# MacSet-L-V2_0_0_2.net
KiCad netlist of a schematic drawn in Altium Designer
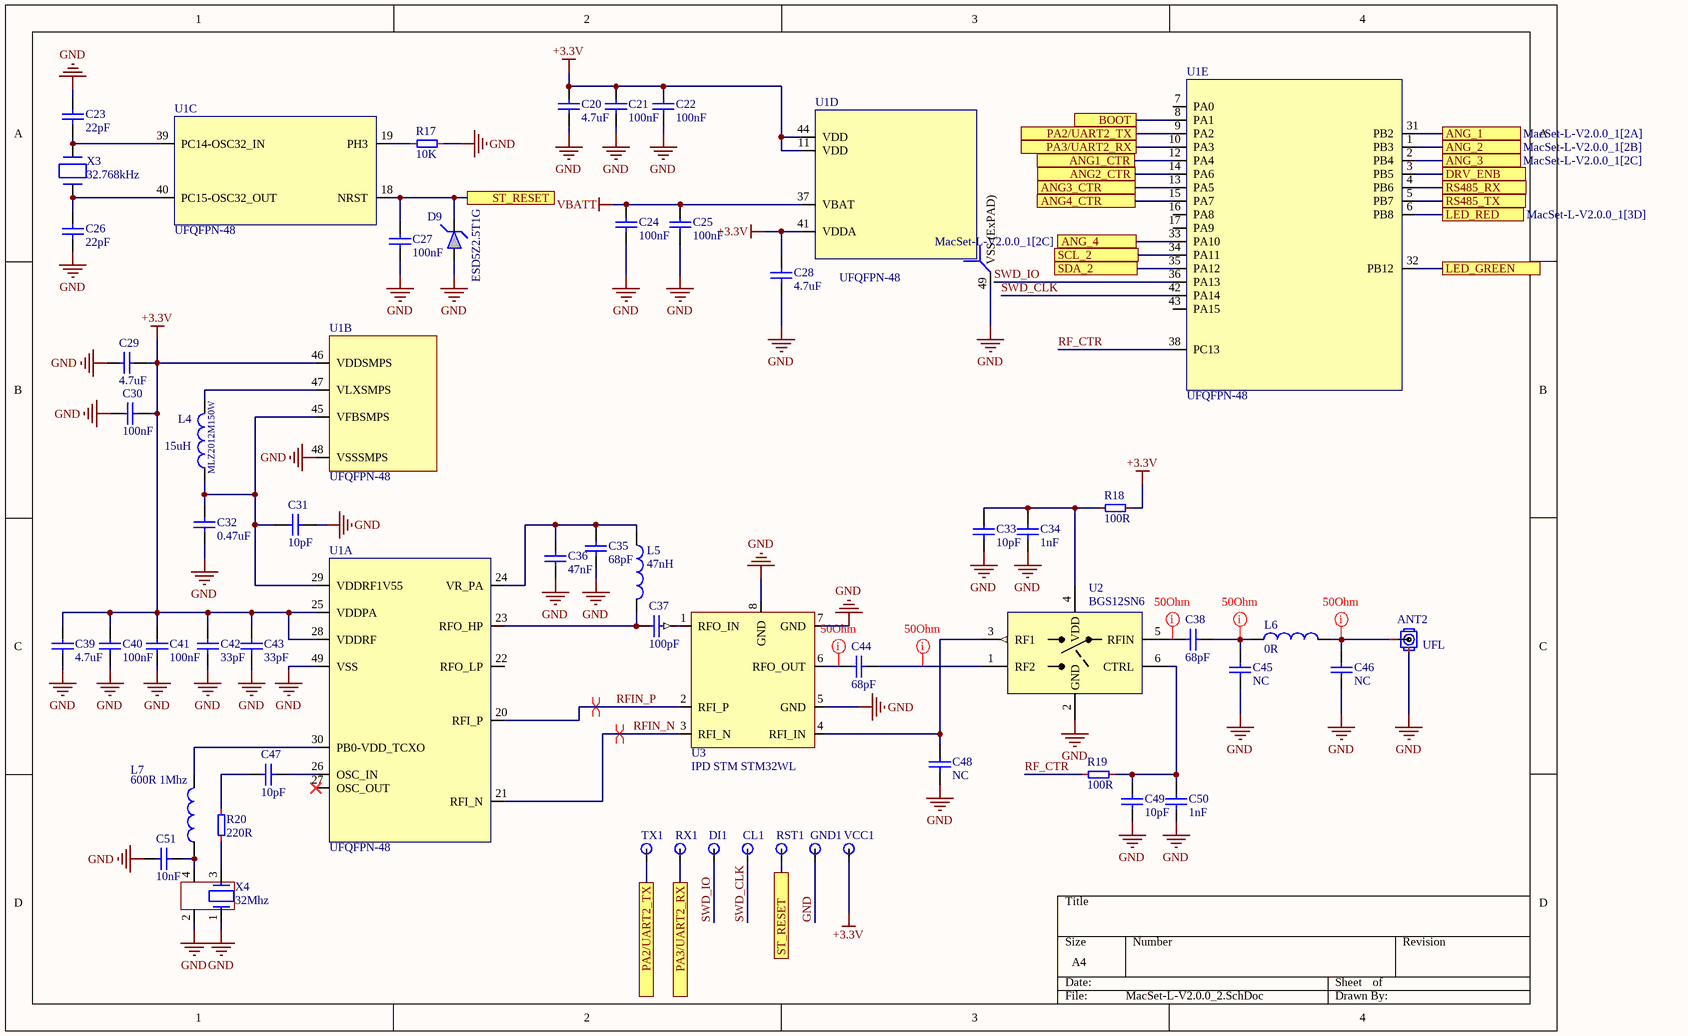
[diagram p0: MacSet-L-V2.0.0_2.SchDoc]

(export (version "E")
  (design (tool "Eeschema 10.0.6"))
  (components
    (comp (ref "ANT2")
      (value "UFL")
      (footprint "UFL")
      (description "SMA Connector")
      (libsource (lib "macnman_3.0") (part "SMA Antenna"))
    )
    (comp (ref "C20")
      (value "4.7uF")
      (footprint "CAP0603")
      (description "MLCC - SMD/SMT 4.7 uF 16 VDC 10% 0603 X5R")
      (fields
        (field (name "MANUFACTURER_PART_NUMBER") "CL10A475KQ8NNNC")
        (field (name "MANUFACTURER") "Samsung Electro-Mechanics")
      )
      (libsource (lib "macnman_2.0") (part "Capa_0603"))
    )
    (comp (ref "C21")
      (value "100nF")
      (footprint "CAP0402")
      (description "Ceramic Capacitor X7R 0402 100nF 16V")
      (fields
        (field (name "MANUFACTURER_PART_NUMBER") "GRM155R71C104JA88D")
        (field (name "MANUFACTURER") "MURATA")
      )
      (libsource (lib "macnman_2.0") (part "Capa_0402"))
    )
    (comp (ref "C22")
      (value "100nF")
      (footprint "CAP0402")
      (description "Ceramic Capacitor X7R 0402 100nF 16V")
      (fields
        (field (name "MANUFACTURER_PART_NUMBER") "GRM155R71C104JA88D")
        (field (name "MANUFACTURER") "MURATA")
      )
      (libsource (lib "macnman_2.0") (part "Capa_0402"))
    )
    (comp (ref "C23")
      (value "22pF")
      (footprint "CAP0402")
      (description "Multilayer Ceramic Capacitors MLCC - SMD/SMT 50 V 22pF C0G 0402 5%")
      (fields
        (field (name "MANUFACTURER_PART_NUMBER") "GCM1555C1H220JA16D")
        (field (name "MANUFACTURER") "Murata")
      )
      (libsource (lib "macnman_2.0") (part "Capa_0402"))
    )
    (comp (ref "C24")
      (value "100nF")
      (footprint "CAP0402")
      (description "Ceramic Capacitor X7R 0402 100nF 16V")
      (fields
        (field (name "MANUFACTURER_PART_NUMBER") "GRM155R71C104JA88D")
        (field (name "MANUFACTURER") "MURATA")
      )
      (libsource (lib "macnman_2.0") (part "Capa_0402"))
    )
    (comp (ref "C25")
      (value "100nF")
      (footprint "CAP0402")
      (description "Ceramic Capacitor X7R 0402 100nF 16V")
      (fields
        (field (name "MANUFACTURER_PART_NUMBER") "GRM155R71C104JA88D")
        (field (name "MANUFACTURER") "MURATA")
      )
      (libsource (lib "macnman_2.0") (part "Capa_0402"))
    )
    (comp (ref "C26")
      (value "22pF")
      (footprint "CAP0402")
      (description "Multilayer Ceramic Capacitors MLCC - SMD/SMT 50 V 22pF C0G 0402 5%")
      (fields
        (field (name "MANUFACTURER_PART_NUMBER") "GCM1555C1H220JA16D")
        (field (name "MANUFACTURER") "Murata")
      )
      (libsource (lib "macnman_2.0") (part "Capa_0402"))
    )
    (comp (ref "C27")
      (value "100nF")
      (footprint "CAP0402")
      (description "Ceramic Capacitor X7R 0402 100nF 16V")
      (fields
        (field (name "MANUFACTURER_PART_NUMBER") "GRM155R71C104JA88D")
        (field (name "MANUFACTURER") "MURATA")
      )
      (libsource (lib "macnman_2.0") (part "Capa_0402"))
    )
    (comp (ref "C28")
      (value "4.7uF")
      (footprint "CAP0603")
      (description "MLCC - SMD/SMT 4.7 uF 16 VDC 10% 0603 X5R")
      (fields
        (field (name "MANUFACTURER_PART_NUMBER") "CL10A475KQ8NNNC")
        (field (name "MANUFACTURER") "Samsung Electro-Mechanics")
      )
      (libsource (lib "macnman_2.0") (part "Capa_0603"))
    )
    (comp (ref "C29")
      (value "4.7uF")
      (footprint "CAP0603")
      (description "MLCC - SMD/SMT 4.7 uF 16 VDC 10% 0603 X5R")
      (fields
        (field (name "MANUFACTURER_PART_NUMBER") "CL10A475KQ8NNNC")
        (field (name "MANUFACTURER") "Samsung Electro-Mechanics")
      )
      (libsource (lib "macnman_2.0") (part "Capa_0603"))
    )
    (comp (ref "C30")
      (value "100nF")
      (footprint "CAP0402")
      (description "Ceramic Capacitor X7R 0402 100nF 16V")
      (fields
        (field (name "MANUFACTURER_PART_NUMBER") "GRM155R71C104JA88D")
        (field (name "MANUFACTURER") "MURATA")
      )
      (libsource (lib "macnman_2.0") (part "Capa_0402"))
    )
    (comp (ref "C31")
      (value "10pF")
      (footprint "CAP0402")
      (description "Multilayer Ceramic Capacitors MLCC - SMD/SMT 50 V 10pF C0G 0402 10%")
      (fields
        (field (name "MANUFACTURER_PART_NUMBER") "CC0402JRNPO9BN100")
        (field (name "MANUFACTURER") "YAGEO")
      )
      (libsource (lib "macnman_2.0") (part "Capa_0402"))
    )
    (comp (ref "C32")
      (value "0.47uF")
      (footprint "CAP0603")
      (description "MLCC - SMD/SMT 0.47 uF 16 VDC 10% 0603 X5R")
      (fields
        (field (name "MANUFACTURER_PART_NUMBER") "CC0603KRX7R0BB474")
        (field (name "MANUFACTURER") "Yageo")
      )
      (libsource (lib "macnman_2.0") (part "Capa_0603"))
    )
    (comp (ref "C33")
      (value "10pF")
      (footprint "CAP0402")
      (description "Multilayer Ceramic Capacitors MLCC - SMD/SMT 50 V 10pF C0G 0402 10%")
      (fields
        (field (name "MANUFACTURER_PART_NUMBER") "CC0402JRNPO9BN100")
        (field (name "MANUFACTURER") "YAGEO")
      )
      (libsource (lib "macnman_2.0") (part "Capa_0402"))
    )
    (comp (ref "C34")
      (value "1nF")
      (footprint "CAP0402")
      (description "Multilayer Ceramic Capacitors MLCC - SMD/SMT 50 V 1nF C0G 0402 10%")
      (fields
        (field (name "MANUFACTURER_PART_NUMBER") "CC0402KRX7R9BB102")
        (field (name "MANUFACTURER") "YAGEO")
      )
      (libsource (lib "macnman_2.0") (part "Capa_0402"))
    )
    (comp (ref "C35")
      (value "68pF")
      (footprint "CAP0402")
      (description "Multilayer Ceramic Capacitors MLCC - SMD/SMT 50 V 68pF C0G 0402 5%")
      (fields
        (field (name "MANUFACTURER_PART_NUMBER") "CC0402JRNPO9BN680")
        (field (name "MANUFACTURER") "YAGEO")
      )
      (libsource (lib "macnman_2.0") (part "Capa_0402"))
    )
    (comp (ref "C36")
      (value "47nF")
      (footprint "CAP0402")
      (description "Multilayer Ceramic Capacitors MLCC - SMD/SMT 50 V 47nF C0G 0402 10%")
      (fields
        (field (name "MANUFACTURER_PART_NUMBER") "0402B473K500CT")
        (field (name "MANUFACTURER") "Walsin")
      )
      (libsource (lib "macnman_2.0") (part "Capa_0402"))
    )
    (comp (ref "C37")
      (value "100pF")
      (footprint "CAP0402")
      (description "Multilayer Ceramic Capacitors MLCC - SMD/SMT 50 V 100pF C0G 0402 10%")
      (fields
        (field (name "MANUFACTURER_PART_NUMBER") "CC0402KRNPO9BN101")
        (field (name "MANUFACTURER") "YAGEO")
      )
      (libsource (lib "") (part "Capa_0402_1"))
    )
    (comp (ref "C38")
      (value "68pF")
      (footprint "CAP0402")
      (description "Multilayer Ceramic Capacitors MLCC - SMD/SMT 50 V 68pF C0G 0402 5%")
      (fields
        (field (name "MANUFACTURER_PART_NUMBER") "CC0402JRNPO9BN680")
        (field (name "MANUFACTURER") "YAGEO")
      )
      (libsource (lib "macnman_2.0") (part "Capa_0402"))
    )
    (comp (ref "C39")
      (value "4.7uF")
      (footprint "CAP0603")
      (description "MLCC - SMD/SMT 4.7 uF 16 VDC 10% 0603 X5R")
      (fields
        (field (name "MANUFACTURER_PART_NUMBER") "CL10A475KQ8NNNC")
        (field (name "MANUFACTURER") "Samsung Electro-Mechanics")
      )
      (libsource (lib "macnman_2.0") (part "Capa_0603"))
    )
    (comp (ref "C40")
      (value "100nF")
      (footprint "CAP0402")
      (description "Ceramic Capacitor X7R 0402 100nF 16V")
      (fields
        (field (name "MANUFACTURER_PART_NUMBER") "GRM155R71C104JA88D")
        (field (name "MANUFACTURER") "MURATA")
      )
      (libsource (lib "macnman_2.0") (part "Capa_0402"))
    )
    (comp (ref "C41")
      (value "100nF")
      (footprint "CAP0402")
      (description "Ceramic Capacitor X7R 0402 100nF 16V")
      (fields
        (field (name "MANUFACTURER_PART_NUMBER") "GRM155R71C104JA88D")
        (field (name "MANUFACTURER") "MURATA")
      )
      (libsource (lib "macnman_2.0") (part "Capa_0402"))
    )
    (comp (ref "C42")
      (value "33pF")
      (footprint "CAP0402")
      (description "Ceramic Capacitor C0G, NP0 0402 33pF 35V")
      (fields
        (field (name "MANUFACTURER_PART_NUMBER") "CC0402JRNPO9BN330")
        (field (name "MANUFACTURER") "MURATA")
      )
      (libsource (lib "macnman_2.0") (part "Capa_0402"))
    )
    (comp (ref "C43")
      (value "33pF")
      (footprint "CAP0402")
      (description "Ceramic Capacitor C0G, NP0 0402 33pF 35V")
      (fields
        (field (name "MANUFACTURER_PART_NUMBER") "CC0402JRNPO9BN330")
        (field (name "MANUFACTURER") "MURATA")
      )
      (libsource (lib "macnman_2.0") (part "Capa_0402"))
    )
    (comp (ref "C44")
      (value "68pF")
      (footprint "CAP0402")
      (description "Multilayer Ceramic Capacitors MLCC - SMD/SMT 50 V 68pF C0G 0402 5%")
      (fields
        (field (name "MANUFACTURER_PART_NUMBER") "CC0402JRNPO9BN680")
        (field (name "MANUFACTURER") "YAGEO")
      )
      (libsource (lib "macnman_2.0") (part "Capa_0402"))
    )
    (comp (ref "C45")
      (value "NC")
      (footprint "CAP0402")
      (description "Multilayer Ceramic Capacitors MLCC - SMD/SMT 50 V 2.4pF C0G 0402 10%")
      (fields
        (field (name "MANUFACTURER_PART_NUMBER") "CC0402CRNPO9BN2R4")
        (field (name "MANUFACTURER") "YAGEO")
      )
      (libsource (lib "macnman_2.0") (part "Capa_0402"))
    )
    (comp (ref "C46")
      (value "NC")
      (footprint "CAP0402")
      (description "Multilayer Ceramic Capacitors MLCC - SMD/SMT 50 V 2.4pF C0G 0402 10%")
      (fields
        (field (name "MANUFACTURER_PART_NUMBER") "CC0402CRNPO9BN2R4")
        (field (name "MANUFACTURER") "YAGEO")
      )
      (libsource (lib "macnman_2.0") (part "Capa_0402"))
    )
    (comp (ref "C47")
      (value "10pF")
      (footprint "CAP0402")
      (description "Multilayer Ceramic Capacitors MLCC - SMD/SMT 50 V 10pF C0G 0402 10%")
      (fields
        (field (name "MANUFACTURER_PART_NUMBER") "CC0402JRNPO9BN100")
        (field (name "MANUFACTURER") "YAGEO")
      )
      (libsource (lib "macnman_2.0") (part "Capa_0402"))
    )
    (comp (ref "C48") (value "NC") (footprint "CAP0402") (libsource (lib "macnman_2.0") (part "Capa_0402")))
    (comp (ref "C49")
      (value "10pF")
      (footprint "CAP0402")
      (description "Multilayer Ceramic Capacitors MLCC - SMD/SMT 50 V 10pF C0G 0402 10%")
      (fields
        (field (name "MANUFACTURER_PART_NUMBER") "CC0402JRNPO9BN100")
        (field (name "MANUFACTURER") "YAGEO")
      )
      (libsource (lib "macnman_2.0") (part "Capa_0402"))
    )
    (comp (ref "C50")
      (value "1nF")
      (footprint "CAP0402")
      (description "Multilayer Ceramic Capacitors MLCC - SMD/SMT 50 V 1nF C0G 0402 10%")
      (fields
        (field (name "MANUFACTURER_PART_NUMBER") "CC0402KRX7R9BB102")
        (field (name "MANUFACTURER") "YAGEO")
      )
      (libsource (lib "macnman_2.0") (part "Capa_0402"))
    )
    (comp (ref "C51")
      (value "10nF")
      (footprint "CAP0402")
      (description "Multilayer Ceramic Capacitors MLCC - SMD/SMT 50 V 10nF C0G 0402 10%")
      (fields
        (field (name "MANUFACTURER_PART_NUMBER") "CC0402KRX7R9BB103")
        (field (name "MANUFACTURER") "YAGEO")
      )
      (libsource (lib "macnman_2.0") (part "Capa_0402"))
    )
    (comp (ref "CL1")
      (value "-")
      (footprint "TH_Pad")
      (description "Through Hole pad 1mm 0.5mm Hole")
      (libsource (lib "macnman_2.0") (part "TH_PAD"))
    )
    (comp (ref "D9")
      (value "ESD5Z2.5T1G")
      (footprint "SOD523")
      (description "ESD Protection Diodes / TVS Diodes 2.5V ESD Protection Unidirectional")
      (fields (field (name "MANUFACTURER") "onsemi"))
      (libsource (lib "macnman_2.0") (part "DIODE-ESD"))
    )
    (comp (ref "DI1")
      (value "-")
      (footprint "TH_Pad")
      (description "Through Hole pad 1mm 0.5mm Hole")
      (libsource (lib "macnman_2.0") (part "TH_PAD"))
    )
    (comp (ref "GND1")
      (value "-")
      (footprint "TH_Pad")
      (description "Through Hole pad 1mm 0.5mm Hole")
      (libsource (lib "macnman_2.0") (part "TH_PAD"))
    )
    (comp (ref "L4")
      (value "15uH")
      (footprint "IND_2012")
      (description "MLZ2012 Multilayer Shielded Inductor 15µH, ±5%")
      (fields (field (name "MANUFACTURER_PART_NUMBER") "MLZ2012M150W") (field (name "MANUFACTURER") "TDK"))
      (libsource (lib "MB1849") (part "Inductor"))
    )
    (comp (ref "L5")
      (value "47nH")
      (footprint "IND_0402")
      (description "47nH High frequency chip inductor ±5%  0402")
      (fields
        (field (name "MANUFACTURER_PART_NUMBER") "LQG15HN47NJ02D")
        (field (name "MANUFACTURER") "Murata")
      )
      (libsource (lib "macnman_2.0") (part "Inductor"))
    )
    (comp (ref "L6")
      (value "0R")
      (footprint "IND_0402")
      (description "Thick Film Resistors - SMD 1/16watt 0R 1% 0402 Commercial Use")
      (fields
        (field (name "MANUFACTURER_PART_NUMBER") "RC0402FR-070RL")
        (field (name "MANUFACTURER") "YAGIO")
      )
      (libsource (lib "macnman_2.0") (part "Inductor"))
    )
    (comp (ref "L7")
      (value "600R 1Mhz")
      (footprint "IND_0402")
      (description "47nH High frequency chip inductor ±5%  0402")
      (fields (field (name "MANUFACTURER_PART_NUMBER") "GZ1005D601TF") (field (name "MANUFACTURER") "Murata"))
      (libsource (lib "macnman_2.0") (part "Inductor"))
    )
    (comp (ref "R17")
      (value "10K")
      (footprint "RESC0402")
      (description "Thick Film Resistors - SMD 1/16watt 10Kohms 0402 1% Commercial Use")
      (fields
        (field (name "MANUFACTURER_PART_NUMBER") "CRCW040210K0FKEDC")
        (field (name "MANUFACTURER") "Vishay")
      )
      (libsource (lib "macnman_2.0") (part "RES_0402"))
    )
    (comp (ref "R18")
      (value "100R")
      (footprint "RESC0402")
      (description "Thin Film Resistors 100 OHM 1% 50PPM 1/1 6W 0402")
      (fields
        (field (name "MANUFACTURER_PART_NUMBER") "RC0402FR-07100RL")
        (field (name "MANUFACTURER") "YAGEO")
      )
      (libsource (lib "macnman_2.0") (part "RES_0402"))
    )
    (comp (ref "R19")
      (value "100R")
      (footprint "RESC0402")
      (description "Thin Film Resistors 100 OHM 1% 50PPM 1/1 6W 0402")
      (fields
        (field (name "MANUFACTURER_PART_NUMBER") "RC0402FR-07100RL")
        (field (name "MANUFACTURER") "YAGEO")
      )
      (libsource (lib "macnman_2.0") (part "RES_0402"))
    )
    (comp (ref "R20")
      (value "220R")
      (footprint "RESC0402")
      (description "Thin Film Resistors 220 OHM 1% 50PPM 1/1 6W 0402")
      (fields
        (field (name "MANUFACTURER_PART_NUMBER") "0402WGF2200TCE")
        (field (name "MANUFACTURER") "Royalohm")
      )
      (libsource (lib "macnman_2.0") (part "RES_0402"))
    )
    (comp (ref "RST1")
      (value "-")
      (footprint "TH_Pad")
      (description "Through Hole pad 1mm 0.5mm Hole")
      (libsource (lib "macnman_2.0") (part "TH_PAD"))
    )
    (comp (ref "RX1")
      (value "-")
      (footprint "TH_Pad")
      (description "Through Hole pad 1mm 0.5mm Hole")
      (libsource (lib "macnman_2.0") (part "TH_PAD"))
    )
    (comp (ref "TX1")
      (value "-")
      (footprint "TH_Pad")
      (description "Through Hole pad 1mm 0.5mm Hole")
      (libsource (lib "macnman_2.0") (part "TH_PAD"))
    )
    (comp (ref "U1")
      (value "UFQFPN-48")
      (footprint "STM32WLxx_QFN48")
      (fields
        (field (name "MANUFACTURER") "STMicroelectronics")
        (field (name "MANUFACTURER_PART_NUMBER") "STM32WL5CCU6")
      )
      (libsource (lib "macnman_3.0") (part "STM32WLE5C8U6_O"))
    )
    (comp (ref "U2")
      (value "BGS12SN6")
      (footprint "SON40P70X40-6N")
      (description "DC switch - Ultra-Low  SPDT analog switch")
      (fields (field (name "MANUFACTURER") "INFINEON"))
      (libsource (lib "macnman_2.0") (part "BGS12SN6"))
    )
    (comp (ref "U3")
      (value "IPD STM STM32WL")
      (footprint "IPD STM")
      (fields
        (field (name "MANUFACTURER") "STMICROELECTRONICS")
        (field (name "MANUFACTURER_PART_NUMBER") "MLPF-WL-02D3")
      )
      (libsource (lib "macnman_3.0") (part "IPD ST STM32WL"))
    )
    (comp (ref "VCC1")
      (value "-")
      (footprint "TH_Pad")
      (description "Through Hole pad 1mm 0.5mm Hole")
      (libsource (lib "macnman_2.0") (part "TH_PAD"))
    )
    (comp (ref "X3")
      (value "32.768kHz")
      (footprint "OSC_3215")
      (description "Crystal Osc 3215 32.768kHz 12pF")
      (fields
        (field (name "MANUFACTURER_PART_NUMBER") "ECS-.327-12.5-34B-TR")
        (field (name "MANUFACTURER") "ECS")
      )
      (libsource (lib "macnman_2.0") (part "OSC_2012"))
    )
    (comp (ref "X4")
      (value "32Mhz")
      (footprint "OSC_2016")
      (description "TCXO Oscillators TG2016SMN 32.0000M-MCGNNM0: TCXO 2.8V 3.3V 0.5PPM -40 85C NON O/E 1K TR")
      (fields
        (field (name "MANUFACTURER_PART_NUMBER") "TG2016SMN 32.0000M-MCGNNM0")
        (field (name "MANUFACTURER") "Epson")
      )
      (libsource (lib "macnman_2.0") (part "OSC_2016"))
    )
  )
  (nets
    (net (code "1") (name "+3.3V") (class "Default")
      (node (ref "C20") (pin "2") (pinfunction "2_2") (pintype "passive"))
      (node (ref "C21") (pin "1") (pinfunction "1_1") (pintype "passive"))
      (node (ref "C22") (pin "1") (pinfunction "1_1") (pintype "passive"))
      (node (ref "C28") (pin "2") (pinfunction "2_2") (pintype "passive"))
      (node (ref "C29") (pin "2") (pinfunction "2_2") (pintype "passive"))
      (node (ref "C30") (pin "1") (pinfunction "1_1") (pintype "passive"))
      (node (ref "C39") (pin "2") (pinfunction "2_2") (pintype "passive"))
      (node (ref "C40") (pin "1") (pinfunction "1_1") (pintype "passive"))
      (node (ref "C41") (pin "1") (pinfunction "1_1") (pintype "passive"))
      (node (ref "C42") (pin "1") (pinfunction "1_1") (pintype "passive"))
      (node (ref "C43") (pin "1") (pinfunction "1_1") (pintype "passive"))
      (node (ref "R18") (pin "1") (pinfunction "1_1") (pintype "passive"))
      (node (ref "U1") (pin "11") (pinfunction "VDD_11") (pintype "passive"))
      (node (ref "U1") (pin "25") (pinfunction "VDDPA_25") (pintype "passive"))
      (node (ref "U1") (pin "28") (pinfunction "VDDRF_28") (pintype "passive"))
      (node (ref "U1") (pin "41") (pinfunction "VDDA_41") (pintype "passive"))
      (node (ref "U1") (pin "44") (pinfunction "VDD_44") (pintype "passive"))
      (node (ref "U1") (pin "46") (pinfunction "VDDSMPS_46") (pintype "passive"))
      (node (ref "VCC1") (pin "1") (pinfunction "RX_1") (pintype "passive"))
    )
    (net (code "2") (name "/ANG1_CTR") (class "Default")
      (node (ref "U1") (pin "12") (pinfunction "PA4_12") (pintype "passive"))
    )
    (net (code "3") (name "/ANG2_CTR") (class "Default")
      (node (ref "U1") (pin "14") (pinfunction "PA6_14") (pintype "passive"))
    )
    (net (code "4") (name "/ANG3_CTR") (class "Default")
      (node (ref "U1") (pin "13") (pinfunction "PA5_13") (pintype "passive"))
    )
    (net (code "5") (name "/ANG4_CTR") (class "Default")
      (node (ref "U1") (pin "15") (pinfunction "PA7_15") (pintype "passive"))
    )
    (net (code "6") (name "/ANG_1") (class "Default")
      (node (ref "U1") (pin "31") (pinfunction "PB2_31") (pintype "passive"))
    )
    (net (code "7") (name "/ANG_2") (class "Default")
      (node (ref "U1") (pin "1") (pinfunction "PB3_1") (pintype "passive"))
    )
    (net (code "8") (name "/ANG_3") (class "Default")
      (node (ref "U1") (pin "2") (pinfunction "PB4_2") (pintype "passive"))
    )
    (net (code "9") (name "/ANG_4") (class "Default")
      (node (ref "U1") (pin "33") (pinfunction "PA10_33") (pintype "passive"))
    )
    (net (code "10") (name "/BOOT") (class "Default")
      (node (ref "U1") (pin "8") (pinfunction "PA1_8") (pintype "passive"))
    )
    (net (code "11") (name "/DRV_ENB") (class "Default")
      (node (ref "U1") (pin "3") (pinfunction "PB5_3") (pintype "passive"))
    )
    (net (code "12") (name "/LED_GREEN") (class "Default")
      (node (ref "U1") (pin "32") (pinfunction "PB12_32") (pintype "passive"))
    )
    (net (code "13") (name "/LED_RED") (class "Default")
      (node (ref "U1") (pin "6") (pinfunction "PB8_6") (pintype "passive"))
    )
    (net (code "14") (name "/PA2{slash}UART2_TX") (class "Default")
      (node (ref "TX1") (pin "1") (pinfunction "RX_1") (pintype "passive"))
      (node (ref "U1") (pin "9") (pinfunction "PA2_9") (pintype "passive"))
    )
    (net (code "15") (name "/PA3{slash}UART2_RX") (class "Default")
      (node (ref "RX1") (pin "1") (pinfunction "RX_1") (pintype "passive"))
      (node (ref "U1") (pin "10") (pinfunction "PA3_10") (pintype "passive"))
    )
    (net (code "16") (name "/RFIN_N") (class "Default")
      (node (ref "U1") (pin "21") (pinfunction "RFI_N_21") (pintype "passive"))
      (node (ref "U3") (pin "3") (pinfunction "RFI_N_3") (pintype "output"))
    )
    (net (code "17") (name "/RFIN_P") (class "Default")
      (node (ref "U1") (pin "20") (pinfunction "RFI_P_20") (pintype "passive"))
      (node (ref "U3") (pin "2") (pinfunction "RFI_P_2") (pintype "output"))
    )
    (net (code "18") (name "/RF_CTR") (class "Default")
      (node (ref "R19") (pin "1") (pinfunction "1_1") (pintype "passive"))
      (node (ref "U1") (pin "38") (pinfunction "PC13_38") (pintype "passive"))
    )
    (net (code "19") (name "/RS485_RX") (class "Default")
      (node (ref "U1") (pin "4") (pinfunction "PB6_4") (pintype "passive"))
    )
    (net (code "20") (name "/RS485_TX") (class "Default")
      (node (ref "U1") (pin "5") (pinfunction "PB7_5") (pintype "passive"))
    )
    (net (code "21") (name "/SCL_2") (class "Default")
      (node (ref "U1") (pin "34") (pinfunction "PA11_34") (pintype "passive"))
    )
    (net (code "22") (name "/SDA_2") (class "Default")
      (node (ref "U1") (pin "35") (pinfunction "PA12_35") (pintype "passive"))
    )
    (net (code "23") (name "/ST_RESET") (class "Default")
      (node (ref "C27") (pin "1") (pinfunction "1_1") (pintype "passive"))
      (node (ref "D9") (pin "1") (pinfunction "K_1") (pintype "passive"))
      (node (ref "RST1") (pin "1") (pinfunction "RX_1") (pintype "passive"))
      (node (ref "U1") (pin "18") (pinfunction "NRST_18") (pintype "passive"))
    )
    (net (code "24") (name "/SWD_CLK") (class "Default")
      (node (ref "CL1") (pin "1") (pinfunction "RX_1") (pintype "passive"))
      (node (ref "U1") (pin "42") (pinfunction "PA14_42") (pintype "passive"))
    )
    (net (code "25") (name "/SWD_IO") (class "Default")
      (node (ref "DI1") (pin "1") (pinfunction "RX_1") (pintype "passive"))
      (node (ref "U1") (pin "36") (pinfunction "PA13_36") (pintype "passive"))
    )
    (net (code "26") (name "GND") (class "Default")
      (node (ref "ANT2") (pin "2") (pinfunction "Value_2") (pintype "passive"))
      (node (ref "C20") (pin "1") (pinfunction "1_1") (pintype "passive"))
      (node (ref "C21") (pin "2") (pinfunction "2_2") (pintype "passive"))
      (node (ref "C22") (pin "2") (pinfunction "2_2") (pintype "passive"))
      (node (ref "C23") (pin "2") (pinfunction "2_2") (pintype "passive"))
      (node (ref "C24") (pin "2") (pinfunction "2_2") (pintype "passive"))
      (node (ref "C25") (pin "2") (pinfunction "2_2") (pintype "passive"))
      (node (ref "C26") (pin "1") (pinfunction "1_1") (pintype "passive"))
      (node (ref "C27") (pin "2") (pinfunction "2_2") (pintype "passive"))
      (node (ref "C28") (pin "1") (pinfunction "1_1") (pintype "passive"))
      (node (ref "C29") (pin "1") (pinfunction "1_1") (pintype "passive"))
      (node (ref "C30") (pin "2") (pinfunction "2_2") (pintype "passive"))
      (node (ref "C31") (pin "1") (pinfunction "1_1") (pintype "passive"))
      (node (ref "C32") (pin "1") (pinfunction "1_1") (pintype "passive"))
      (node (ref "C33") (pin "1") (pinfunction "1_1") (pintype "passive"))
      (node (ref "C34") (pin "1") (pinfunction "1_1") (pintype "passive"))
      (node (ref "C35") (pin "1") (pinfunction "1_1") (pintype "passive"))
      (node (ref "C36") (pin "1") (pinfunction "1_1") (pintype "passive"))
      (node (ref "C39") (pin "1") (pinfunction "1_1") (pintype "passive"))
      (node (ref "C40") (pin "2") (pinfunction "2_2") (pintype "passive"))
      (node (ref "C41") (pin "2") (pinfunction "2_2") (pintype "passive"))
      (node (ref "C42") (pin "2") (pinfunction "2_2") (pintype "passive"))
      (node (ref "C43") (pin "2") (pinfunction "2_2") (pintype "passive"))
      (node (ref "C45") (pin "1") (pinfunction "1_1") (pintype "passive"))
      (node (ref "C46") (pin "1") (pinfunction "1_1") (pintype "passive"))
      (node (ref "C48") (pin "2") (pinfunction "2_2") (pintype "passive"))
      (node (ref "C49") (pin "1") (pinfunction "1_1") (pintype "passive"))
      (node (ref "C50") (pin "1") (pinfunction "1_1") (pintype "passive"))
      (node (ref "C51") (pin "2") (pinfunction "2_2") (pintype "passive"))
      (node (ref "D9") (pin "2") (pinfunction "A_2") (pintype "passive"))
      (node (ref "GND1") (pin "1") (pinfunction "RX_1") (pintype "passive"))
      (node (ref "R17") (pin "1") (pinfunction "1_1") (pintype "passive"))
      (node (ref "U1") (pin "48") (pinfunction "VSSSMPS_48") (pintype "passive"))
      (node (ref "U1") (pin "49") (pinfunction "VSS_49") (pintype "passive"))
      (node (ref "U2") (pin "2") (pinfunction "GND_2") (pintype "passive"))
      (node (ref "U3") (pin "5") (pinfunction "GND_5") (pintype "power_in"))
      (node (ref "U3") (pin "7") (pinfunction "GND_7") (pintype "power_in"))
      (node (ref "U3") (pin "8") (pinfunction "GND_8") (pintype "power_in"))
      (node (ref "X4") (pin "1") (pinfunction "1_1") (pintype "passive"))
      (node (ref "X4") (pin "2") (pinfunction "2_2") (pintype "passive"))
    )
    (net (code "27") (name "Net-(ANT2-Value-Pad1)") (class "Default")
      (node (ref "ANT2") (pin "1") (pinfunction "Value_1") (pintype "passive"))
      (node (ref "C46") (pin "2") (pinfunction "2_2") (pintype "passive"))
      (node (ref "L6") (pin "2") (pintype "passive"))
    )
    (net (code "28") (name "Net-(C38-Pad1)") (class "Default")
      (node (ref "C38") (pin "1") (pinfunction "1_1") (pintype "passive"))
      (node (ref "C45") (pin "2") (pinfunction "2_2") (pintype "passive"))
      (node (ref "L6") (pin "1") (pintype "passive"))
    )
    (net (code "29") (name "Net-(C47-Pad1)") (class "Default")
      (node (ref "C47") (pin "1") (pinfunction "1_1") (pintype "passive"))
      (node (ref "R20") (pin "2") (pinfunction "2_2") (pintype "passive"))
    )
    (net (code "30") (name "Net-(C51-Pad1)") (class "Default")
      (node (ref "C51") (pin "1") (pinfunction "1_1") (pintype "passive"))
      (node (ref "L7") (pin "1") (pintype "passive"))
      (node (ref "X4") (pin "4") (pinfunction "4_4") (pintype "passive"))
    )
    (net (code "31") (name "Net-(R20-Pad1)") (class "Default")
      (node (ref "R20") (pin "1") (pinfunction "1_1") (pintype "passive"))
      (node (ref "X4") (pin "3") (pinfunction "3_3") (pintype "passive"))
    )
    (net (code "32") (name "Net-(U1A-OSC_IN)") (class "Default")
      (node (ref "C47") (pin "2") (pinfunction "2_2") (pintype "passive"))
      (node (ref "U1") (pin "26") (pinfunction "OSC_IN_26") (pintype "passive"))
    )
    (net (code "33") (name "Net-(U1A-PB0-VDD_TCXO)") (class "Default")
      (node (ref "L7") (pin "2") (pintype "passive"))
      (node (ref "U1") (pin "30") (pinfunction "PB0-VDD_TCXO_30") (pintype "passive"))
    )
    (net (code "34") (name "Net-(U1A-RFO_HP)") (class "Default")
      (node (ref "C37") (pin "2") (pinfunction "2_2") (pintype "passive"))
      (node (ref "L5") (pin "2") (pintype "passive"))
      (node (ref "U1") (pin "23") (pinfunction "RFO_HP_23") (pintype "passive"))
    )
    (net (code "35") (name "Net-(U1A-VDDRF1V55)") (class "Default")
      (node (ref "C31") (pin "2") (pinfunction "2_2") (pintype "passive"))
      (node (ref "C32") (pin "2") (pinfunction "2_2") (pintype "passive"))
      (node (ref "L4") (pin "1") (pinfunction "1_1") (pintype "passive"))
      (node (ref "U1") (pin "29") (pinfunction "VDDRF1V55_29") (pintype "passive"))
      (node (ref "U1") (pin "45") (pinfunction "VFBSMPS_45") (pintype "passive"))
    )
    (net (code "36") (name "Net-(U1A-VR_PA)") (class "Default")
      (node (ref "C35") (pin "2") (pinfunction "2_2") (pintype "passive"))
      (node (ref "C36") (pin "2") (pinfunction "2_2") (pintype "passive"))
      (node (ref "L5") (pin "1") (pintype "passive"))
      (node (ref "U1") (pin "24") (pinfunction "VR_PA_24") (pintype "passive"))
    )
    (net (code "37") (name "Net-(U1B-VLXSMPS)") (class "Default")
      (node (ref "L4") (pin "2") (pinfunction "2_2") (pintype "passive"))
      (node (ref "U1") (pin "47") (pinfunction "VLXSMPS_47") (pintype "passive"))
    )
    (net (code "38") (name "Net-(U1C-PC14-OSC32_IN)") (class "Default")
      (node (ref "C23") (pin "1") (pinfunction "1_1") (pintype "passive"))
      (node (ref "U1") (pin "39") (pinfunction "PC14-OSC32_IN_39") (pintype "passive"))
      (node (ref "X3") (pin "2") (pinfunction "X2_2") (pintype "passive"))
    )
    (net (code "39") (name "Net-(U1C-PC15-OSC32_OUT)") (class "Default")
      (node (ref "C26") (pin "2") (pinfunction "2_2") (pintype "passive"))
      (node (ref "U1") (pin "40") (pinfunction "PC15-OSC32_OUT_40") (pintype "passive"))
      (node (ref "X3") (pin "1") (pinfunction "X1_1") (pintype "passive"))
    )
    (net (code "40") (name "Net-(U1C-PH3)") (class "Default")
      (node (ref "R17") (pin "2") (pinfunction "2_2") (pintype "passive"))
      (node (ref "U1") (pin "19") (pinfunction "PH3_19") (pintype "passive"))
    )
    (net (code "41") (name "Net-(U2-CTRL)") (class "Default")
      (node (ref "C49") (pin "2") (pinfunction "2_2") (pintype "passive"))
      (node (ref "C50") (pin "2") (pinfunction "2_2") (pintype "passive"))
      (node (ref "R19") (pin "2") (pinfunction "2_2") (pintype "passive"))
      (node (ref "U2") (pin "6") (pinfunction "CTRL_6") (pintype "passive"))
    )
    (net (code "42") (name "Net-(U2-RF1)") (class "Default")
      (node (ref "C48") (pin "1") (pinfunction "1_1") (pintype "passive"))
      (node (ref "U2") (pin "3") (pinfunction "RF1_3") (pintype "output"))
      (node (ref "U3") (pin "4") (pinfunction "RFI_IN_4") (pintype "input"))
    )
    (net (code "43") (name "Net-(U2-RF2)") (class "Default")
      (node (ref "C44") (pin "1") (pinfunction "1_1") (pintype "passive"))
      (node (ref "U2") (pin "1") (pinfunction "RF2_1") (pintype "passive"))
    )
    (net (code "44") (name "Net-(U2-RFIN)") (class "Default")
      (node (ref "C38") (pin "2") (pinfunction "2_2") (pintype "passive"))
      (node (ref "U2") (pin "5") (pinfunction "RFIN_5") (pintype "passive"))
    )
    (net (code "45") (name "Net-(U2-VDD)") (class "Default")
      (node (ref "C33") (pin "2") (pinfunction "2_2") (pintype "passive"))
      (node (ref "C34") (pin "2") (pinfunction "2_2") (pintype "passive"))
      (node (ref "R18") (pin "2") (pinfunction "2_2") (pintype "passive"))
      (node (ref "U2") (pin "4") (pinfunction "VDD_4") (pintype "passive"))
    )
    (net (code "46") (name "Net-(U3-RFO_IN)") (class "Default")
      (node (ref "C37") (pin "1") (pinfunction "1_1") (pintype "output"))
      (node (ref "U3") (pin "1") (pinfunction "RFO_IN_1") (pintype "input"))
    )
    (net (code "47") (name "Net-(U3-RFO_OUT)") (class "Default")
      (node (ref "C44") (pin "2") (pinfunction "2_2") (pintype "passive"))
      (node (ref "U3") (pin "6") (pinfunction "RFO_OUT_6") (pintype "output"))
    )
    (net (code "48") (name "VBATT") (class "Default")
      (node (ref "C24") (pin "1") (pinfunction "1_1") (pintype "passive"))
      (node (ref "C25") (pin "1") (pinfunction "1_1") (pintype "passive"))
      (node (ref "U1") (pin "37") (pinfunction "VBAT_37") (pintype "passive"))
    )
    (net (code "49") (name "unconnected-(U1A-OSC_OUT-Pad27)") (class "Default")
      (node (ref "U1") (pin "27") (pinfunction "OSC_OUT_27") (pintype "passive+no_connect"))
    )
    (net (code "50") (name "unconnected-(U1A-RFO_LP-Pad22)") (class "Default")
      (node (ref "U1") (pin "22") (pinfunction "RFO_LP_22") (pintype "passive"))
    )
    (net (code "51") (name "unconnected-(U1E-PA0-Pad7)") (class "Default")
      (node (ref "U1") (pin "7") (pinfunction "PA0_7") (pintype "passive"))
    )
    (net (code "52") (name "unconnected-(U1E-PA8-Pad16)") (class "Default")
      (node (ref "U1") (pin "16") (pinfunction "PA8_16") (pintype "passive"))
    )
    (net (code "53") (name "unconnected-(U1E-PA9-Pad17)") (class "Default")
      (node (ref "U1") (pin "17") (pinfunction "PA9_17") (pintype "passive"))
    )
    (net (code "54") (name "unconnected-(U1E-PA15-Pad43)") (class "Default")
      (node (ref "U1") (pin "43") (pinfunction "PA15_43") (pintype "passive"))
    )
  )
)
